# OneBoard.net
KiCad netlist of a schematic drawn in EAGLE
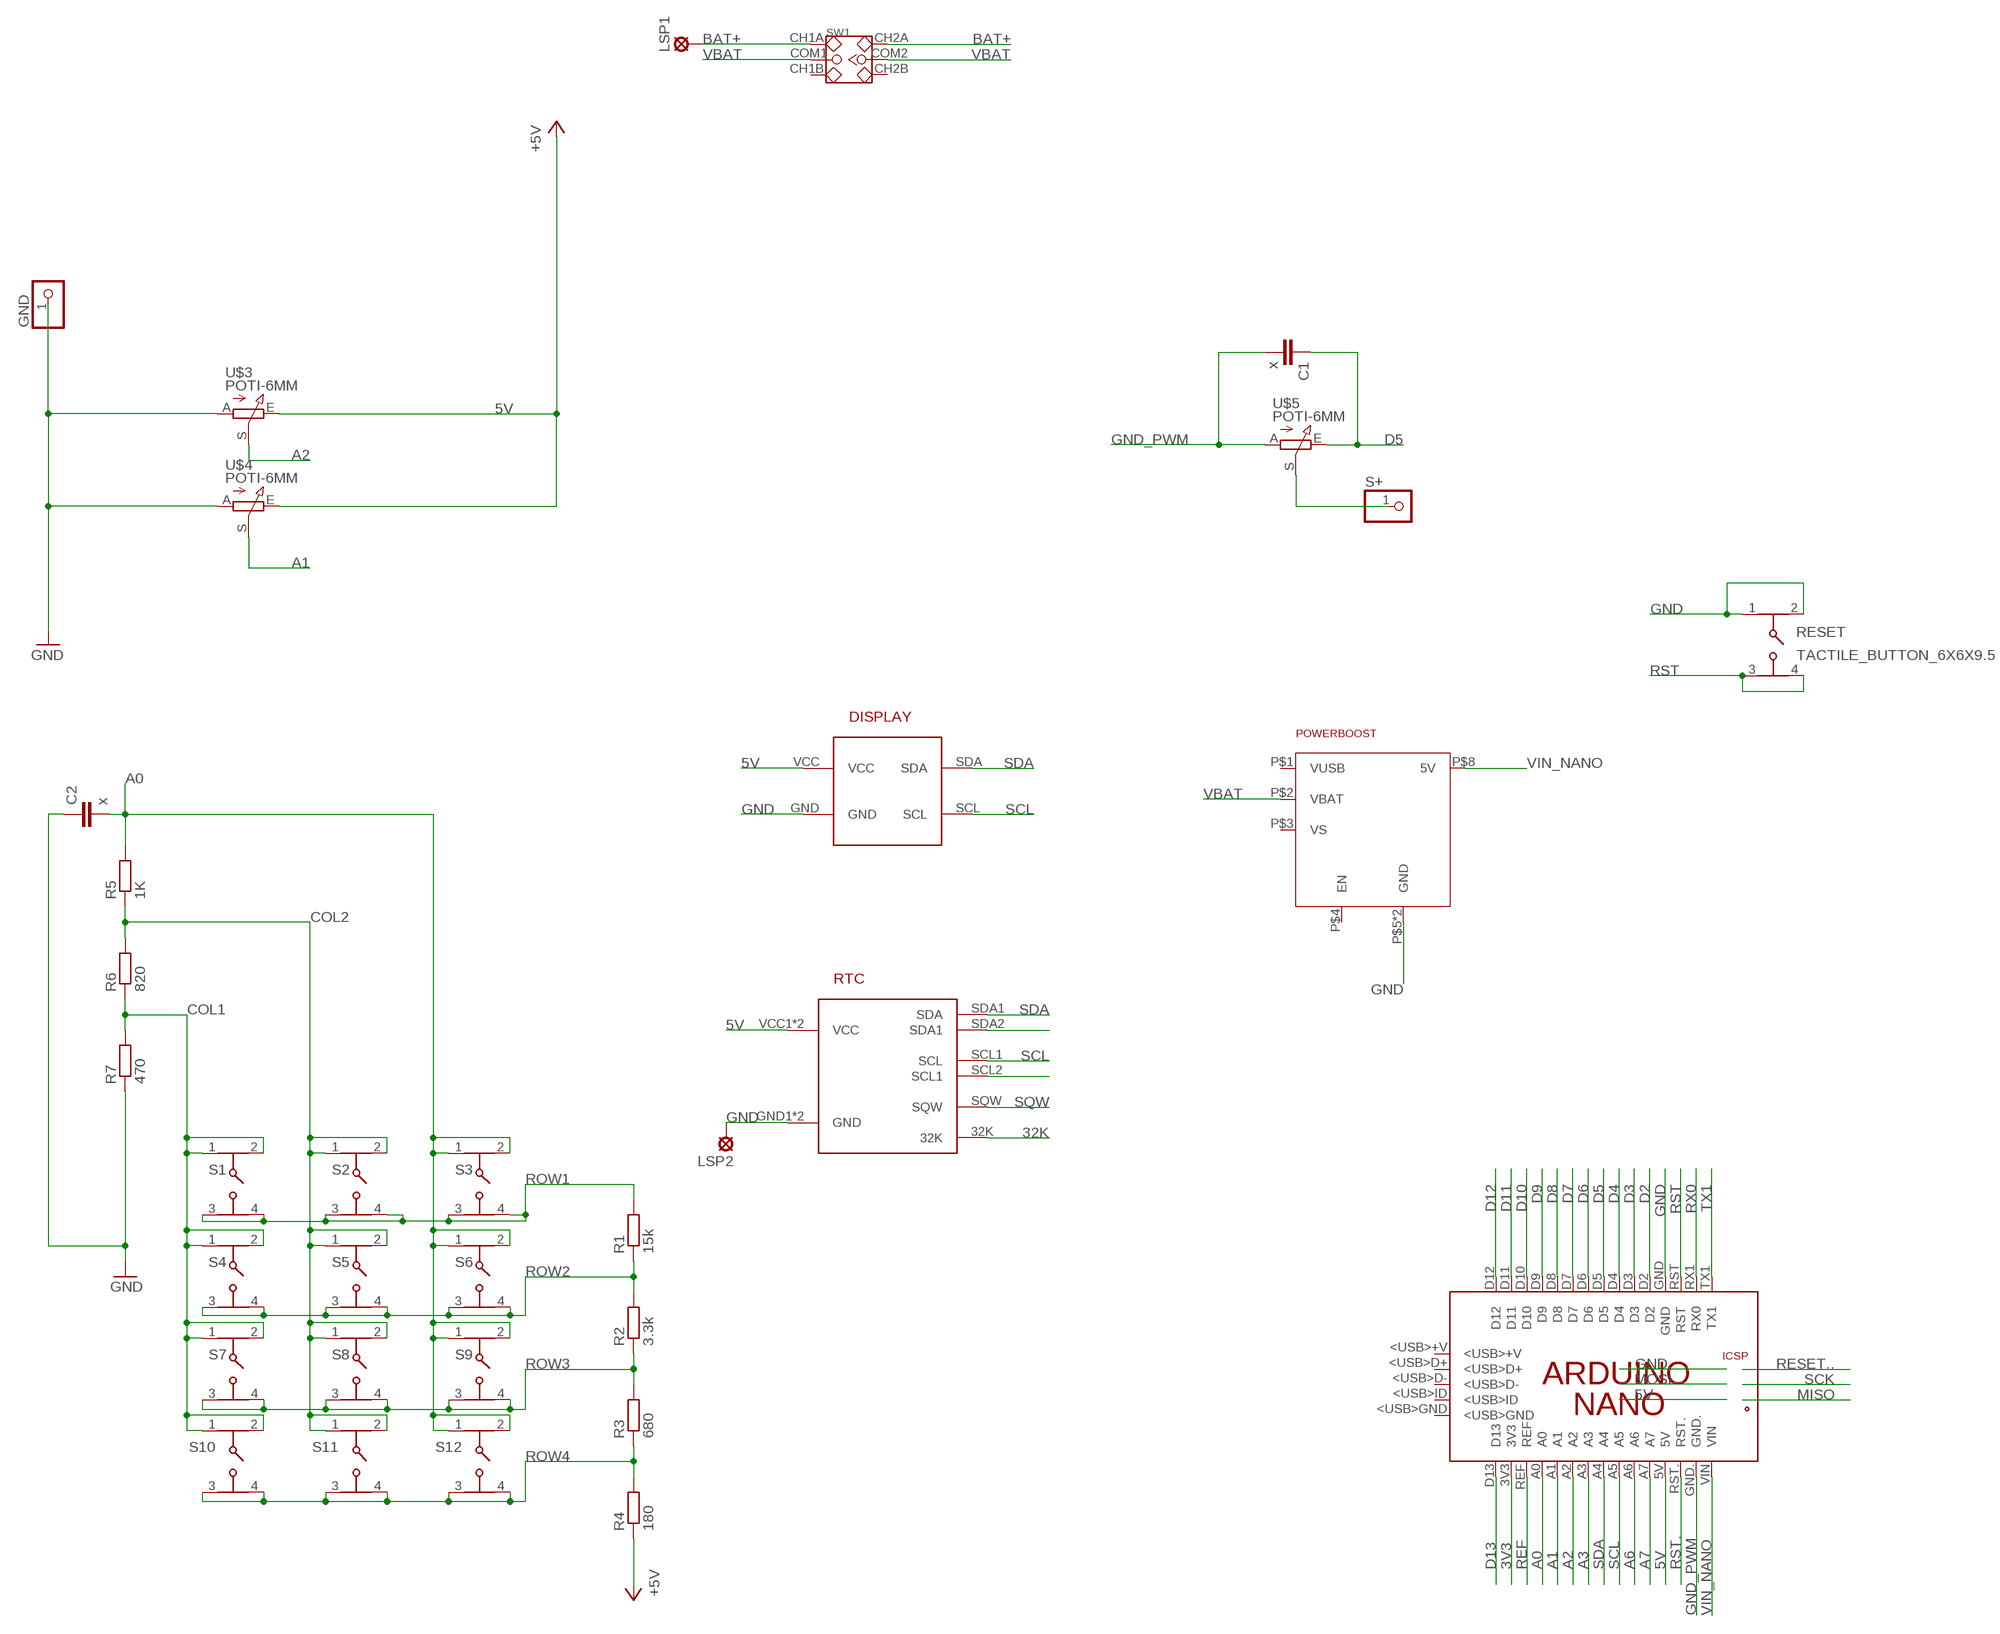
[diagram p0: schematic, sheet 1]

(export (version "E")
  (design (tool "Eeschema 10.0.6"))
  (components
    (comp (ref "C1")
      (value "x")
      (footprint "eagle-import:C025-025X050")
      (libsource (lib "eagle-import") (part "C-EU025-025X050"))
    )
    (comp (ref "C2")
      (value "x")
      (footprint "eagle-import:C025-025X050")
      (libsource (lib "eagle-import") (part "C-EU025-025X050"))
    )
    (comp (ref "DISPLAY")
      (value "OLED_BREAKOUT")
      (footprint "eagle-import:OLED_128X32_BREAKOUT")
      (libsource (lib "eagle-import") (part "OLED_BREAKOUT"))
    )
    (comp (ref "GND")
      (value "PINHD-1X1")
      (footprint "eagle-import:1X01")
      (libsource (lib "eagle-import") (part "PINHD-1X1"))
    )
    (comp (ref "LSP1")
      (value "LSP11")
      (footprint "eagle-import:LSP11")
      (libsource (lib "eagle-import") (part "LSP11"))
    )
    (comp (ref "LSP2")
      (value "LSP11")
      (footprint "eagle-import:LSP11")
      (libsource (lib "eagle-import") (part "LSP11"))
    )
    (comp (ref "POWERBOOST")
      (value "ADAFRUIT_POWERBOOST_1000C")
      (footprint "eagle-import:ADAFRUIT_POWERBOOST_1000C")
      (libsource (lib "eagle-import") (part "ADAFRUIT_POWERBOOST_1000C"))
    )
    (comp (ref "R1")
      (value "15k")
      (footprint "eagle-import:R0603")
      (libsource (lib "eagle-import") (part "R-EU_R0603"))
    )
    (comp (ref "R2")
      (value "3.3k")
      (footprint "eagle-import:R0603")
      (libsource (lib "eagle-import") (part "R-EU_R0603"))
    )
    (comp (ref "R3")
      (value "680")
      (footprint "eagle-import:R0603")
      (libsource (lib "eagle-import") (part "R-EU_R0603"))
    )
    (comp (ref "R4")
      (value "180")
      (footprint "eagle-import:R0603")
      (libsource (lib "eagle-import") (part "R-EU_R0603"))
    )
    (comp (ref "R5")
      (value "1K")
      (footprint "eagle-import:R0603")
      (libsource (lib "eagle-import") (part "R-EU_R0603"))
    )
    (comp (ref "R6")
      (value "820")
      (footprint "eagle-import:R0603")
      (libsource (lib "eagle-import") (part "R-EU_R0603"))
    )
    (comp (ref "R7")
      (value "470")
      (footprint "eagle-import:R0603")
      (libsource (lib "eagle-import") (part "R-EU_R0603"))
    )
    (comp (ref "RESET")
      (value "TACTILE_BUTTON_6X6X9.5")
      (footprint "eagle-import:TACTILE_SWITCH_PTH_6.0MM")
      (libsource (lib "eagle-import") (part "TACTILE_BUTTON_6X6X9.5"))
    )
    (comp (ref "RTC")
      (value "DS3231_BREAKOUT")
      (footprint "eagle-import:DS3231_BREAKOUT")
      (libsource (lib "eagle-import") (part "DS3231_BREAKOUT"))
    )
    (comp (ref "S+")
      (value "PINHD-1X1")
      (footprint "eagle-import:1X01")
      (libsource (lib "eagle-import") (part "PINHD-1X1"))
    )
    (comp (ref "S1")
      (value "TACTILE_BUTTON_6X6X9.5")
      (footprint "eagle-import:TACTILE_SWITCH_PTH_6.0MM")
      (libsource (lib "eagle-import") (part "TACTILE_BUTTON_6X6X9.5"))
    )
    (comp (ref "S2")
      (value "TACTILE_BUTTON_6X6X9.5")
      (footprint "eagle-import:TACTILE_SWITCH_PTH_6.0MM")
      (libsource (lib "eagle-import") (part "TACTILE_BUTTON_6X6X9.5"))
    )
    (comp (ref "S3")
      (value "TACTILE_BUTTON_6X6X9.5")
      (footprint "eagle-import:TACTILE_SWITCH_PTH_6.0MM")
      (libsource (lib "eagle-import") (part "TACTILE_BUTTON_6X6X9.5"))
    )
    (comp (ref "S4")
      (value "TACTILE_BUTTON_6X6X9.5")
      (footprint "eagle-import:TACTILE_SWITCH_PTH_6.0MM")
      (libsource (lib "eagle-import") (part "TACTILE_BUTTON_6X6X9.5"))
    )
    (comp (ref "S5")
      (value "TACTILE_BUTTON_6X6X9.5")
      (footprint "eagle-import:TACTILE_SWITCH_PTH_6.0MM")
      (libsource (lib "eagle-import") (part "TACTILE_BUTTON_6X6X9.5"))
    )
    (comp (ref "S6")
      (value "TACTILE_BUTTON_6X6X9.5")
      (footprint "eagle-import:TACTILE_SWITCH_PTH_6.0MM")
      (libsource (lib "eagle-import") (part "TACTILE_BUTTON_6X6X9.5"))
    )
    (comp (ref "S7")
      (value "TACTILE_BUTTON_6X6X9.5")
      (footprint "eagle-import:TACTILE_SWITCH_PTH_6.0MM")
      (libsource (lib "eagle-import") (part "TACTILE_BUTTON_6X6X9.5"))
    )
    (comp (ref "S8")
      (value "TACTILE_BUTTON_6X6X9.5")
      (footprint "eagle-import:TACTILE_SWITCH_PTH_6.0MM")
      (libsource (lib "eagle-import") (part "TACTILE_BUTTON_6X6X9.5"))
    )
    (comp (ref "S9")
      (value "TACTILE_BUTTON_6X6X9.5")
      (footprint "eagle-import:TACTILE_SWITCH_PTH_6.0MM")
      (libsource (lib "eagle-import") (part "TACTILE_BUTTON_6X6X9.5"))
    )
    (comp (ref "S10")
      (value "TACTILE_BUTTON_6X6X9.5")
      (footprint "eagle-import:TACTILE_SWITCH_PTH_6.0MM")
      (libsource (lib "eagle-import") (part "TACTILE_BUTTON_6X6X9.5"))
    )
    (comp (ref "S11")
      (value "TACTILE_BUTTON_6X6X9.5")
      (footprint "eagle-import:TACTILE_SWITCH_PTH_6.0MM")
      (libsource (lib "eagle-import") (part "TACTILE_BUTTON_6X6X9.5"))
    )
    (comp (ref "S12")
      (value "TACTILE_BUTTON_6X6X9.5")
      (footprint "eagle-import:TACTILE_SWITCH_PTH_6.0MM")
      (libsource (lib "eagle-import") (part "TACTILE_BUTTON_6X6X9.5"))
    )
    (comp (ref "SW1")
      (value "DIP-TOGGLE-SWITCH-2CH-(2X3P-2.54)")
      (footprint "eagle-import:SW6-2.54-9.0X3.5X3.2+2.0MM")
      (fields (field (name "MPN") "MS-22D18 G2 ROHS"))
      (libsource (lib "eagle-import") (part "DIP-TOGGLE-SWITCH-2CH-(2X3P-2.54)"))
    )
    (comp (ref "U$3")
      (value "POTI-6MM")
      (footprint "eagle-import:POTI-6MM")
      (libsource (lib "eagle-import") (part "POTI-6MM"))
    )
    (comp (ref "U$4")
      (value "POTI-6MM")
      (footprint "eagle-import:POTI-6MM")
      (libsource (lib "eagle-import") (part "POTI-6MM"))
    )
    (comp (ref "U$5")
      (value "POTI-6MM")
      (footprint "eagle-import:POTI-6MM")
      (libsource (lib "eagle-import") (part "POTI-6MM"))
    )
    (comp (ref "U$7")
      (value "ARDUINO-NANO")
      (footprint "eagle-import:ARDUINO_NANO")
      (libsource (lib "eagle-import") (part "ARDUINO-NANO"))
    )
  )
  (nets
    (net (code "1") (name "+5V") (class "Default")
      (node (ref "DISPLAY") (pin "VCC") (pinfunction "VCC_VCC") (pintype "bidirectional"))
      (node (ref "R4") (pin "1") (pinfunction "1_1") (pintype "passive"))
      (node (ref "RTC") (pin "VCC1") (pinfunction "VCC_VCC1") (pintype "bidirectional"))
      (node (ref "RTC") (pin "VCC2") (pinfunction "VCC_VCC2") (pintype "bidirectional"))
      (node (ref "U$3") (pin "E") (pinfunction "E_E") (pintype "passive"))
      (node (ref "U$4") (pin "E") (pinfunction "E_E") (pintype "passive"))
      (node (ref "U$7") (pin "5V") (pinfunction "5V_5V") (pintype "bidirectional"))
      (node (ref "U$7") (pin "5V.") (pinfunction "5V._5V.") (pintype "bidirectional"))
    )
    (net (code "2") (name "/3V3") (class "Default")
      (node (ref "U$7") (pin "3V3") (pinfunction "3V3_3V3") (pintype "bidirectional"))
    )
    (net (code "3") (name "/32K") (class "Default")
      (node (ref "RTC") (pin "32K") (pinfunction "32K_32K") (pintype "bidirectional"))
    )
    (net (code "4") (name "/A0") (class "Default")
      (node (ref "C2") (pin "2") (pinfunction "2_2") (pintype "passive"))
      (node (ref "R5") (pin "2") (pinfunction "2_2") (pintype "passive"))
      (node (ref "S12") (pin "1") (pinfunction "1_1") (pintype "passive"))
      (node (ref "S12") (pin "2") (pinfunction "3_2") (pintype "passive"))
      (node (ref "S3") (pin "1") (pinfunction "1_1") (pintype "passive"))
      (node (ref "S3") (pin "2") (pinfunction "3_2") (pintype "passive"))
      (node (ref "S6") (pin "1") (pinfunction "1_1") (pintype "passive"))
      (node (ref "S6") (pin "2") (pinfunction "3_2") (pintype "passive"))
      (node (ref "S9") (pin "1") (pinfunction "1_1") (pintype "passive"))
      (node (ref "S9") (pin "2") (pinfunction "3_2") (pintype "passive"))
      (node (ref "U$7") (pin "A0") (pinfunction "A0_A0") (pintype "bidirectional"))
    )
    (net (code "5") (name "/A1") (class "Default")
      (node (ref "U$4") (pin "S") (pinfunction "S_S") (pintype "passive"))
      (node (ref "U$7") (pin "A1") (pinfunction "A1_A1") (pintype "bidirectional"))
    )
    (net (code "6") (name "/A2") (class "Default")
      (node (ref "U$3") (pin "S") (pinfunction "S_S") (pintype "passive"))
      (node (ref "U$7") (pin "A2") (pinfunction "A2_A2") (pintype "bidirectional"))
    )
    (net (code "7") (name "/A3") (class "Default")
      (node (ref "U$7") (pin "A3") (pinfunction "A3_A3") (pintype "bidirectional"))
    )
    (net (code "8") (name "/A6") (class "Default")
      (node (ref "U$7") (pin "A6") (pinfunction "A6_A6") (pintype "bidirectional"))
    )
    (net (code "9") (name "/A7") (class "Default")
      (node (ref "U$7") (pin "A7") (pinfunction "A7_A7") (pintype "bidirectional"))
    )
    (net (code "10") (name "/BAT+") (class "Default")
      (node (ref "LSP1") (pin "MP") (pinfunction "MP_MP") (pintype "passive"))
      (node (ref "SW1") (pin "CH1A") (pinfunction "CH1A_CH1A") (pintype "bidirectional"))
      (node (ref "SW1") (pin "CH2A") (pinfunction "CH2A_CH2A") (pintype "bidirectional"))
    )
    (net (code "11") (name "/COL1") (class "Default")
      (node (ref "R6") (pin "1") (pinfunction "1_1") (pintype "passive"))
      (node (ref "R7") (pin "2") (pinfunction "2_2") (pintype "passive"))
      (node (ref "S1") (pin "1") (pinfunction "1_1") (pintype "passive"))
      (node (ref "S1") (pin "2") (pinfunction "3_2") (pintype "passive"))
      (node (ref "S10") (pin "1") (pinfunction "1_1") (pintype "passive"))
      (node (ref "S10") (pin "2") (pinfunction "3_2") (pintype "passive"))
      (node (ref "S4") (pin "1") (pinfunction "1_1") (pintype "passive"))
      (node (ref "S4") (pin "2") (pinfunction "3_2") (pintype "passive"))
      (node (ref "S7") (pin "1") (pinfunction "1_1") (pintype "passive"))
      (node (ref "S7") (pin "2") (pinfunction "3_2") (pintype "passive"))
    )
    (net (code "12") (name "/COL2") (class "Default")
      (node (ref "R5") (pin "1") (pinfunction "1_1") (pintype "passive"))
      (node (ref "R6") (pin "2") (pinfunction "2_2") (pintype "passive"))
      (node (ref "S11") (pin "1") (pinfunction "1_1") (pintype "passive"))
      (node (ref "S11") (pin "2") (pinfunction "3_2") (pintype "passive"))
      (node (ref "S2") (pin "1") (pinfunction "1_1") (pintype "passive"))
      (node (ref "S2") (pin "2") (pinfunction "3_2") (pintype "passive"))
      (node (ref "S5") (pin "1") (pinfunction "1_1") (pintype "passive"))
      (node (ref "S5") (pin "2") (pinfunction "3_2") (pintype "passive"))
      (node (ref "S8") (pin "1") (pinfunction "1_1") (pintype "passive"))
      (node (ref "S8") (pin "2") (pinfunction "3_2") (pintype "passive"))
    )
    (net (code "13") (name "/D2") (class "Default")
      (node (ref "U$7") (pin "D2") (pinfunction "D2_D2") (pintype "bidirectional"))
    )
    (net (code "14") (name "/D3") (class "Default")
      (node (ref "U$7") (pin "D3") (pinfunction "D3_D3") (pintype "bidirectional"))
    )
    (net (code "15") (name "/D4") (class "Default")
      (node (ref "U$7") (pin "D4") (pinfunction "D4_D4") (pintype "bidirectional"))
    )
    (net (code "16") (name "/D5") (class "Default")
      (node (ref "C1") (pin "1") (pinfunction "1_1") (pintype "passive"))
      (node (ref "U$5") (pin "E") (pinfunction "E_E") (pintype "passive"))
      (node (ref "U$7") (pin "D5") (pinfunction "D5_D5") (pintype "bidirectional"))
    )
    (net (code "17") (name "/D6") (class "Default")
      (node (ref "U$7") (pin "D6") (pinfunction "D6_D6") (pintype "bidirectional"))
    )
    (net (code "18") (name "/D7") (class "Default")
      (node (ref "U$7") (pin "D7") (pinfunction "D7_D7") (pintype "bidirectional"))
    )
    (net (code "19") (name "/D8") (class "Default")
      (node (ref "U$7") (pin "D8") (pinfunction "D8_D8") (pintype "bidirectional"))
    )
    (net (code "20") (name "/D9") (class "Default")
      (node (ref "U$7") (pin "D9") (pinfunction "D9_D9") (pintype "bidirectional"))
    )
    (net (code "21") (name "/D10") (class "Default")
      (node (ref "U$7") (pin "D10") (pinfunction "D10_D10") (pintype "bidirectional"))
    )
    (net (code "22") (name "/D11") (class "Default")
      (node (ref "U$7") (pin "D11") (pinfunction "D11_D11") (pintype "bidirectional"))
    )
    (net (code "23") (name "/D12") (class "Default")
      (node (ref "U$7") (pin "D12") (pinfunction "D12_D12") (pintype "bidirectional"))
    )
    (net (code "24") (name "/D13") (class "Default")
      (node (ref "U$7") (pin "D13") (pinfunction "D13_D13") (pintype "bidirectional"))
    )
    (net (code "25") (name "/GND_PWM") (class "Default")
      (node (ref "C1") (pin "2") (pinfunction "2_2") (pintype "passive"))
      (node (ref "U$5") (pin "A") (pinfunction "A_A") (pintype "passive"))
      (node (ref "U$7") (pin "GND.") (pinfunction "GND._GND.") (pintype "bidirectional"))
    )
    (net (code "26") (name "/MISO") (class "Default")
      (node (ref "U$7") (pin "MISO") (pinfunction "MISO_MISO") (pintype "bidirectional"))
    )
    (net (code "27") (name "/MOSI") (class "Default")
      (node (ref "U$7") (pin "MOSI") (pinfunction "MOSI_MOSI") (pintype "bidirectional"))
    )
    (net (code "28") (name "/REF") (class "Default")
      (node (ref "U$7") (pin "REF") (pinfunction "REF_REF") (pintype "bidirectional"))
    )
    (net (code "29") (name "/RESET..") (class "Default")
      (node (ref "U$7") (pin "RESET..") (pinfunction "RESET.._RESET..") (pintype "bidirectional"))
    )
    (net (code "30") (name "/ROW1") (class "Default")
      (node (ref "R1") (pin "2") (pinfunction "2_2") (pintype "passive"))
      (node (ref "S1") (pin "3") (pinfunction "2_3") (pintype "passive"))
      (node (ref "S1") (pin "4") (pinfunction "4_4") (pintype "passive"))
      (node (ref "S2") (pin "3") (pinfunction "2_3") (pintype "passive"))
      (node (ref "S2") (pin "4") (pinfunction "4_4") (pintype "passive"))
      (node (ref "S3") (pin "3") (pinfunction "2_3") (pintype "passive"))
      (node (ref "S3") (pin "4") (pinfunction "4_4") (pintype "passive"))
    )
    (net (code "31") (name "/ROW2") (class "Default")
      (node (ref "R1") (pin "1") (pinfunction "1_1") (pintype "passive"))
      (node (ref "R2") (pin "2") (pinfunction "2_2") (pintype "passive"))
      (node (ref "S4") (pin "3") (pinfunction "2_3") (pintype "passive"))
      (node (ref "S4") (pin "4") (pinfunction "4_4") (pintype "passive"))
      (node (ref "S5") (pin "3") (pinfunction "2_3") (pintype "passive"))
      (node (ref "S5") (pin "4") (pinfunction "4_4") (pintype "passive"))
      (node (ref "S6") (pin "3") (pinfunction "2_3") (pintype "passive"))
      (node (ref "S6") (pin "4") (pinfunction "4_4") (pintype "passive"))
    )
    (net (code "32") (name "/ROW3") (class "Default")
      (node (ref "R2") (pin "1") (pinfunction "1_1") (pintype "passive"))
      (node (ref "R3") (pin "2") (pinfunction "2_2") (pintype "passive"))
      (node (ref "S7") (pin "3") (pinfunction "2_3") (pintype "passive"))
      (node (ref "S7") (pin "4") (pinfunction "4_4") (pintype "passive"))
      (node (ref "S8") (pin "3") (pinfunction "2_3") (pintype "passive"))
      (node (ref "S8") (pin "4") (pinfunction "4_4") (pintype "passive"))
      (node (ref "S9") (pin "3") (pinfunction "2_3") (pintype "passive"))
      (node (ref "S9") (pin "4") (pinfunction "4_4") (pintype "passive"))
    )
    (net (code "33") (name "/ROW4") (class "Default")
      (node (ref "R3") (pin "1") (pinfunction "1_1") (pintype "passive"))
      (node (ref "R4") (pin "2") (pinfunction "2_2") (pintype "passive"))
      (node (ref "S10") (pin "3") (pinfunction "2_3") (pintype "passive"))
      (node (ref "S10") (pin "4") (pinfunction "4_4") (pintype "passive"))
      (node (ref "S11") (pin "3") (pinfunction "2_3") (pintype "passive"))
      (node (ref "S11") (pin "4") (pinfunction "4_4") (pintype "passive"))
      (node (ref "S12") (pin "3") (pinfunction "2_3") (pintype "passive"))
      (node (ref "S12") (pin "4") (pinfunction "4_4") (pintype "passive"))
    )
    (net (code "34") (name "/RST") (class "Default")
      (node (ref "RESET") (pin "3") (pinfunction "2_3") (pintype "passive"))
      (node (ref "RESET") (pin "4") (pinfunction "4_4") (pintype "passive"))
      (node (ref "U$7") (pin "RST") (pinfunction "RST_RST") (pintype "bidirectional"))
    )
    (net (code "35") (name "/RST.") (class "Default")
      (node (ref "U$7") (pin "RST.") (pinfunction "RST._RST.") (pintype "bidirectional"))
    )
    (net (code "36") (name "/RX0") (class "Default")
      (node (ref "U$7") (pin "RX1") (pinfunction "RX0_RX1") (pintype "bidirectional"))
    )
    (net (code "37") (name "/SCK") (class "Default")
      (node (ref "U$7") (pin "SCK") (pinfunction "SCK_SCK") (pintype "bidirectional"))
    )
    (net (code "38") (name "/SCL") (class "Default")
      (node (ref "DISPLAY") (pin "SCL") (pinfunction "SCL_SCL") (pintype "bidirectional"))
      (node (ref "RTC") (pin "SCL1") (pinfunction "SCL_SCL1") (pintype "bidirectional"))
      (node (ref "U$7") (pin "A5") (pinfunction "A5_A5") (pintype "bidirectional"))
    )
    (net (code "39") (name "/SDA") (class "Default")
      (node (ref "DISPLAY") (pin "SDA") (pinfunction "SDA_SDA") (pintype "bidirectional"))
      (node (ref "RTC") (pin "SDA1") (pinfunction "SDA_SDA1") (pintype "bidirectional"))
      (node (ref "U$7") (pin "A4") (pinfunction "A4_A4") (pintype "bidirectional"))
    )
    (net (code "40") (name "/SQW") (class "Default")
      (node (ref "RTC") (pin "SQW") (pinfunction "SQW_SQW") (pintype "bidirectional"))
    )
    (net (code "41") (name "/TX1") (class "Default")
      (node (ref "U$7") (pin "TX1") (pinfunction "TX1_TX1") (pintype "bidirectional"))
    )
    (net (code "42") (name "/VBAT") (class "Default")
      (node (ref "POWERBOOST") (pin "P$2") (pinfunction "VBAT_P$2") (pintype "power_in"))
      (node (ref "SW1") (pin "COM1") (pinfunction "COM1_COM1") (pintype "bidirectional"))
      (node (ref "SW1") (pin "COM2") (pinfunction "COM2_COM2") (pintype "bidirectional"))
    )
    (net (code "43") (name "/VIN_NANO") (class "Default")
      (node (ref "POWERBOOST") (pin "P$8") (pinfunction "5V_P$8") (pintype "bidirectional"))
      (node (ref "U$7") (pin "VIN") (pinfunction "VIN_VIN") (pintype "bidirectional"))
    )
    (net (code "44") (name "/VS") (class "Default")
      (node (ref "POWERBOOST") (pin "P$3") (pinfunction "VS_P$3") (pintype "power_in"))
    )
    (net (code "45") (name "/VUSB") (class "Default")
      (node (ref "POWERBOOST") (pin "P$1") (pinfunction "VUSB_P$1") (pintype "power_in"))
    )
    (net (code "46") (name "GND") (class "Default")
      (node (ref "C2") (pin "1") (pinfunction "1_1") (pintype "passive"))
      (node (ref "DISPLAY") (pin "GND") (pinfunction "GND_GND") (pintype "bidirectional"))
      (node (ref "GND") (pin "1") (pinfunction "1_1") (pintype "passive"))
      (node (ref "LSP2") (pin "MP") (pinfunction "MP_MP") (pintype "passive"))
      (node (ref "POWERBOOST") (pin "P$5") (pinfunction "GND_P$5") (pintype "power_in"))
      (node (ref "POWERBOOST") (pin "P$7") (pinfunction "GND_P$7") (pintype "power_in"))
      (node (ref "R7") (pin "1") (pinfunction "1_1") (pintype "passive"))
      (node (ref "RESET") (pin "1") (pinfunction "1_1") (pintype "passive"))
      (node (ref "RESET") (pin "2") (pinfunction "3_2") (pintype "passive"))
      (node (ref "RTC") (pin "GND1") (pinfunction "GND_GND1") (pintype "bidirectional"))
      (node (ref "RTC") (pin "GND2") (pinfunction "GND_GND2") (pintype "bidirectional"))
      (node (ref "U$3") (pin "A") (pinfunction "A_A") (pintype "passive"))
      (node (ref "U$4") (pin "A") (pinfunction "A_A") (pintype "passive"))
      (node (ref "U$7") (pin "GND") (pinfunction "GND_GND") (pintype "bidirectional"))
      (node (ref "U$7") (pin "GND_") (pinfunction "GND__GND_") (pintype "bidirectional"))
    )
    (net (code "47") (name "Net-(S+-Pad1)") (class "Default")
      (node (ref "S+") (pin "1") (pinfunction "1_1") (pintype "passive"))
      (node (ref "U$5") (pin "S") (pinfunction "S_S") (pintype "passive"))
    )
    (net (code "48") (name "unconnected-(POWERBOOST-EN-PadP$4)") (class "Default")
      (node (ref "POWERBOOST") (pin "P$4") (pinfunction "EN_P$4") (pintype "bidirectional"))
    )
    (net (code "49") (name "unconnected-(RTC-SCL1-PadSCL2)") (class "Default")
      (node (ref "RTC") (pin "SCL2") (pinfunction "SCL1_SCL2") (pintype "bidirectional"))
    )
    (net (code "50") (name "unconnected-(RTC-SDA1-PadSDA2)") (class "Default")
      (node (ref "RTC") (pin "SDA2") (pinfunction "SDA1_SDA2") (pintype "bidirectional"))
    )
    (net (code "51") (name "unconnected-(SW1-PadCH1B)") (class "Default")
      (node (ref "SW1") (pin "CH1B") (pinfunction "CH1B_CH1B") (pintype "bidirectional"))
    )
    (net (code "52") (name "unconnected-(SW1-PadCH2B)") (class "Default")
      (node (ref "SW1") (pin "CH2B") (pinfunction "CH2B_CH2B") (pintype "bidirectional"))
    )
    (net (code "53") (name "unconnected-(U$7-Pad<USB>+V)") (class "Default")
      (node (ref "U$7") (pin "<USB>+V") (pinfunction "<USB>+V_<USB>+V") (pintype "bidirectional"))
    )
    (net (code "54") (name "unconnected-(U$7-Pad<USB>D+)") (class "Default")
      (node (ref "U$7") (pin "<USB>D+") (pinfunction "<USB>D+_<USB>D+") (pintype "bidirectional"))
    )
    (net (code "55") (name "unconnected-(U$7-Pad<USB>D-)") (class "Default")
      (node (ref "U$7") (pin "<USB>D-") (pinfunction "<USB>D-_<USB>D-") (pintype "bidirectional"))
    )
    (net (code "56") (name "unconnected-(U$7-Pad<USB>GND)") (class "Default")
      (node (ref "U$7") (pin "<USB>GND") (pinfunction "<USB>GND_<USB>GND") (pintype "bidirectional"))
    )
    (net (code "57") (name "unconnected-(U$7-Pad<USB>ID)") (class "Default")
      (node (ref "U$7") (pin "<USB>ID") (pinfunction "<USB>ID_<USB>ID") (pintype "bidirectional"))
    )
  )
)
